# STM32_F4VE.net
KiCad netlist of a schematic drawn in Altium Designer
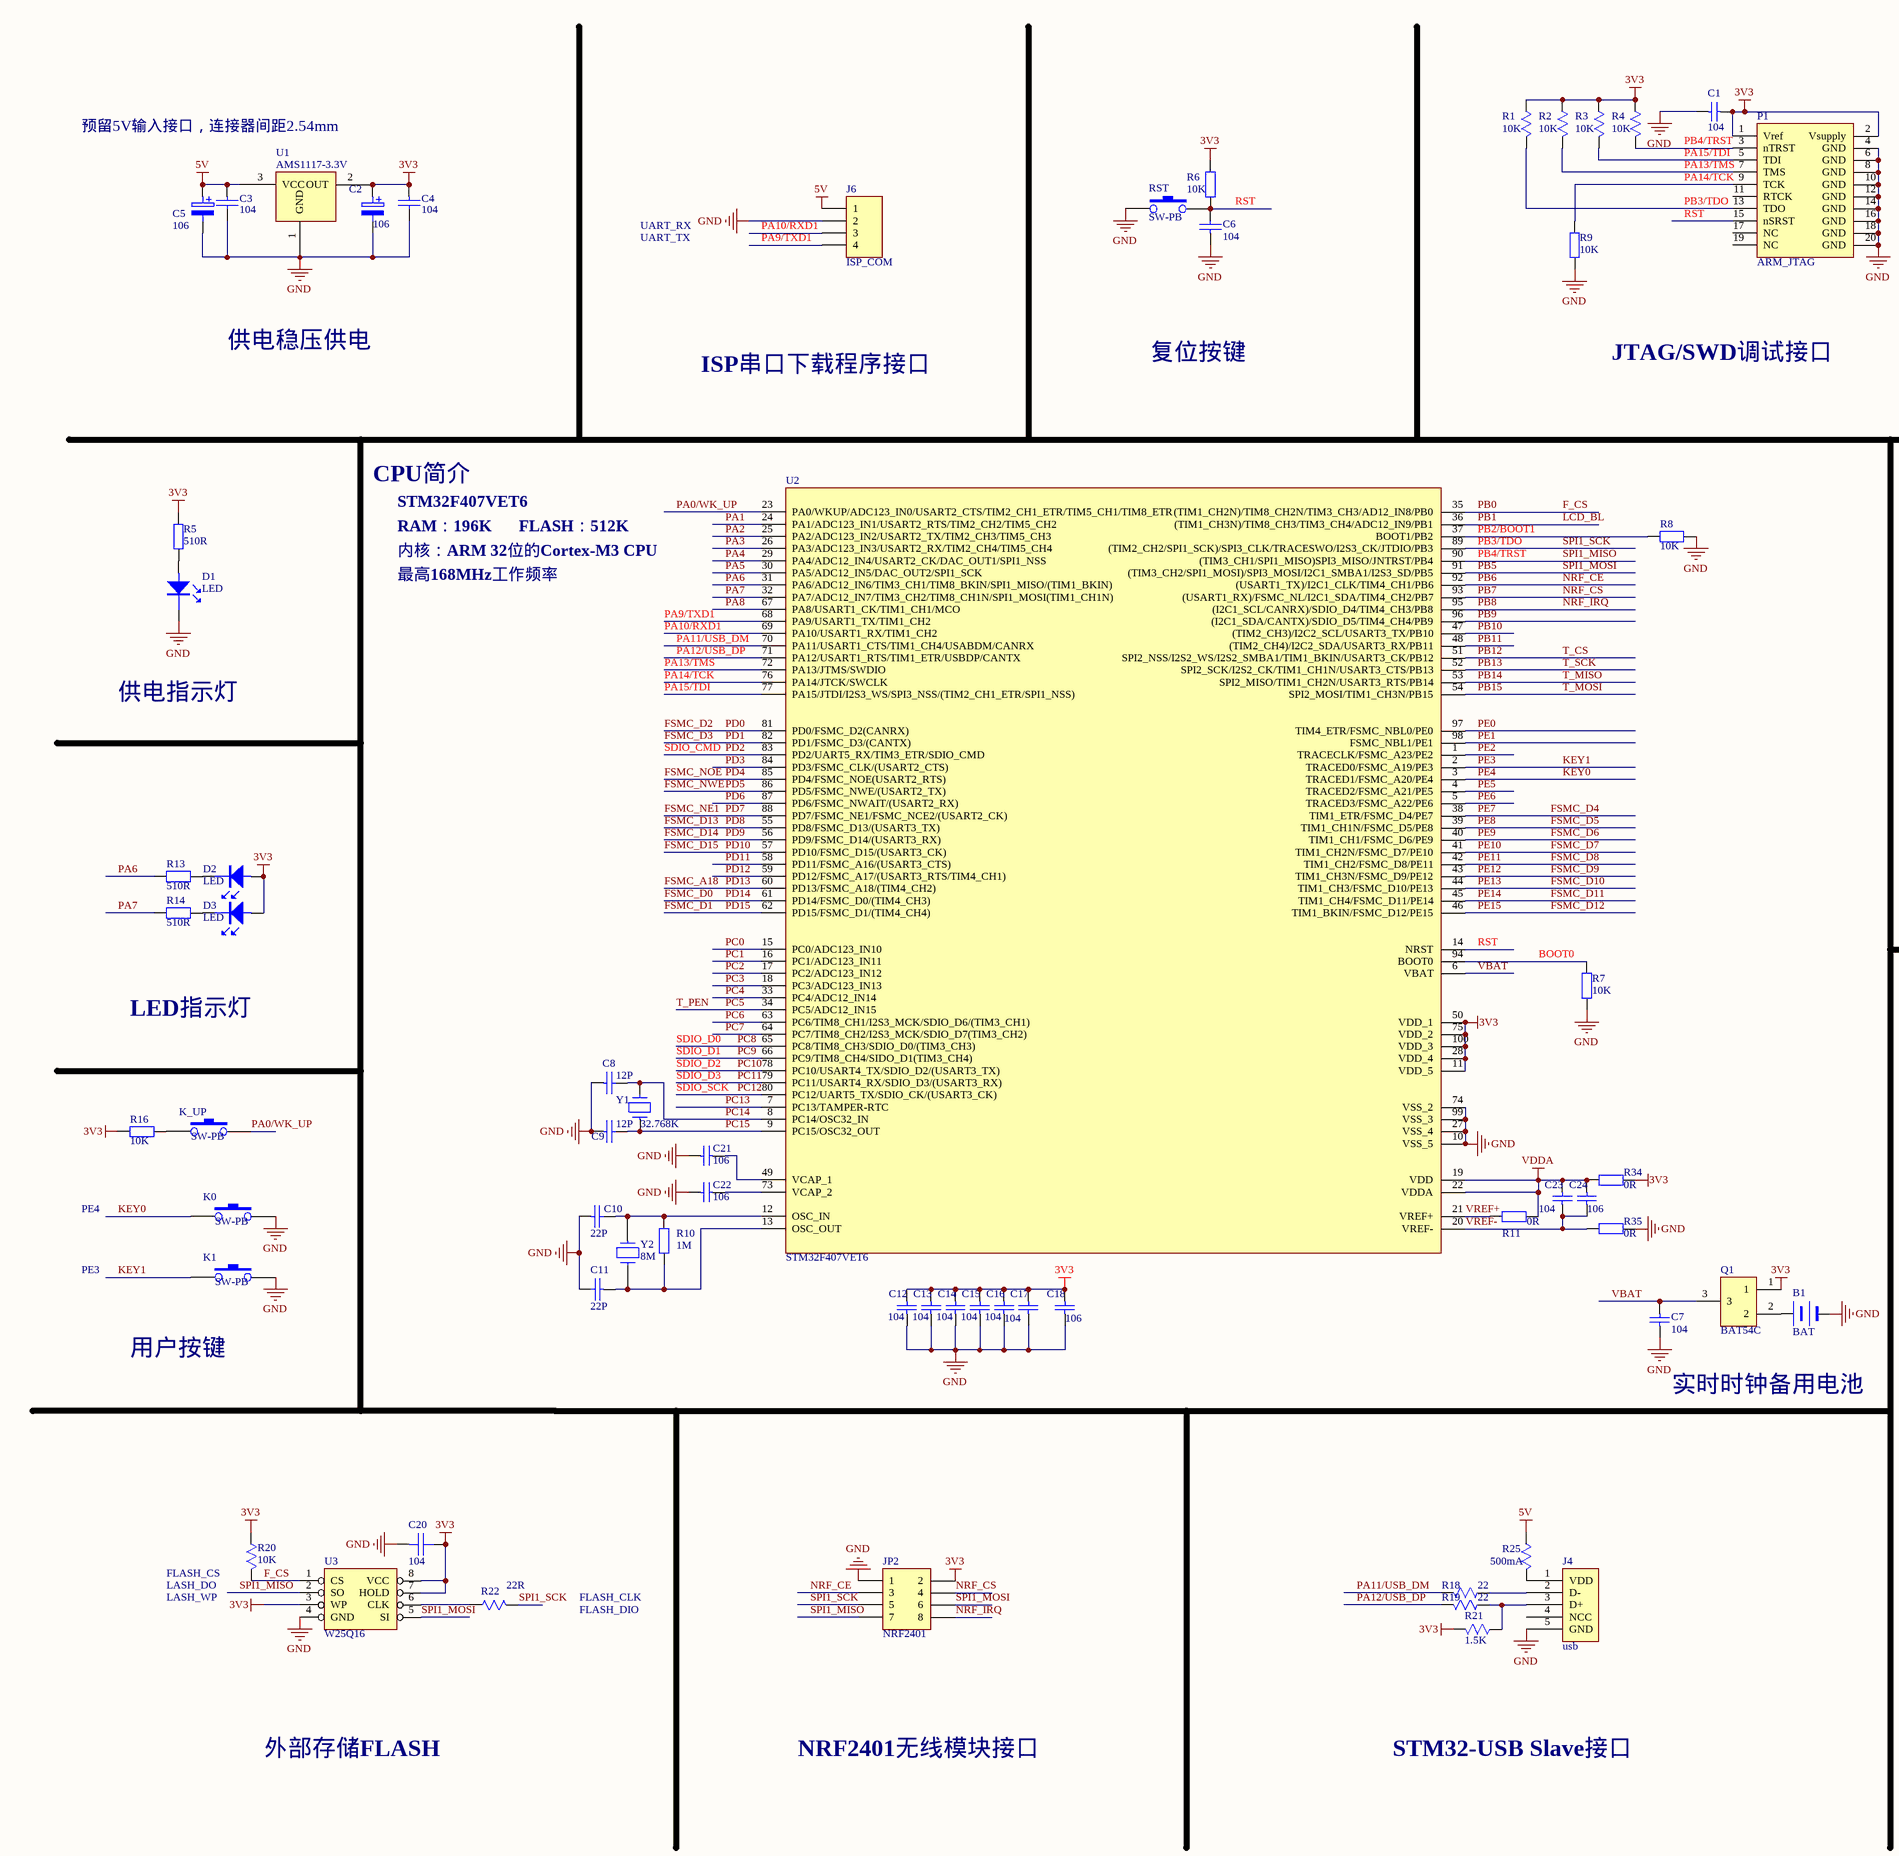
[diagram p0: STM32_F4VE.SchDoc, left]
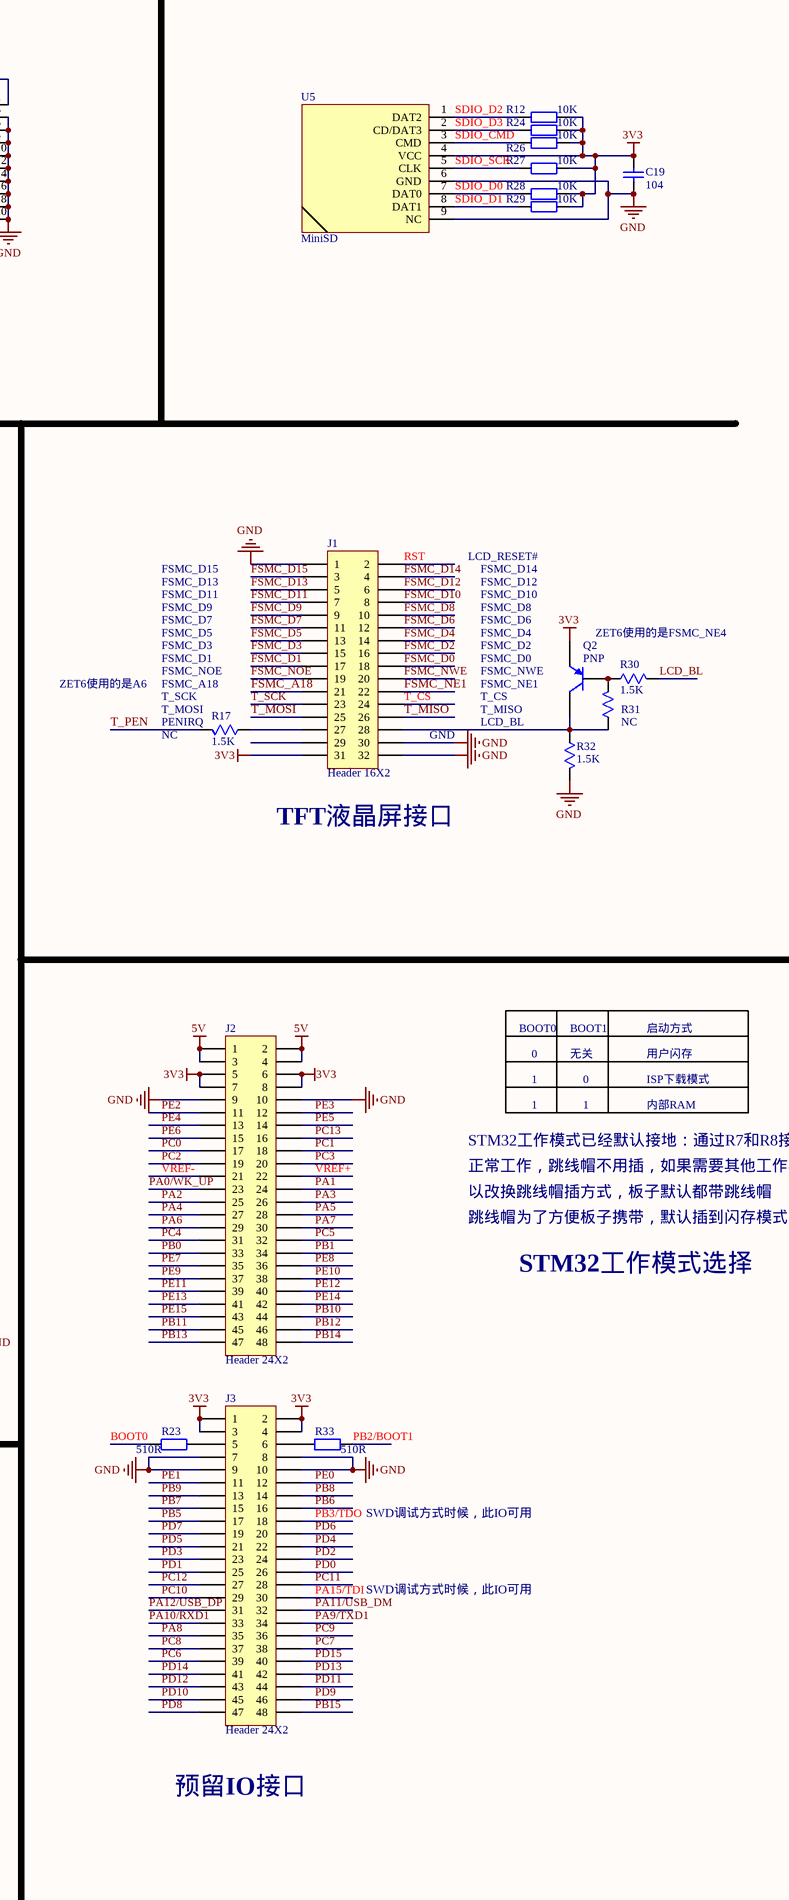
[diagram p1: STM32_F4VE.SchDoc, right]

(export (version "E")
  (design (tool "Eeschema 10.0.6"))
  (components
    (comp (ref "B1") (value "BAT") (footprint "BAT") (libsource (lib "*") (part "BATTERY")))
    (comp (ref "C1")
      (value "104")
      (footprint "RC0603")
      (description "Capacitor")
      (fields (field (name "PUBLISHER") "Altium Limited"))
      (libsource (lib "*") (part "Cap"))
    )
    (comp (ref "C2") (value "106") (footprint "RC0805") (libsource (lib "*") (part "ELECTRO2")))
    (comp (ref "C3")
      (value "104")
      (footprint "RC0603")
      (description "Capacitor")
      (libsource (lib "*") (part "CAP"))
    )
    (comp (ref "C4")
      (value "104")
      (footprint "RC0603")
      (description "Capacitor")
      (libsource (lib "*") (part "CAP"))
    )
    (comp (ref "C5") (value "106") (footprint "RC0805") (libsource (lib "*") (part "ELECTRO2")))
    (comp (ref "C6")
      (value "104")
      (footprint "RC0603")
      (description "Capacitor")
      (libsource (lib "") (part "CAP_1"))
    )
    (comp (ref "C7")
      (value "104")
      (footprint "RC0603")
      (description "Capacitor")
      (fields (field (name "PUBLISHER") "Altium Limited"))
      (libsource (lib "") (part "Cap_1"))
    )
    (comp (ref "C8") (value "12P") (footprint "RC0603") (libsource (lib "") (part "CAP_2")))
    (comp (ref "C9") (value "12P") (footprint "RC0603") (libsource (lib "") (part "CAP_2")))
    (comp (ref "C10")
      (value "22P")
      (footprint "RC0603")
      (description "Capacitor")
      (libsource (lib "") (part "CAP_1"))
    )
    (comp (ref "C11")
      (value "22P")
      (footprint "RC0603")
      (description "Capacitor")
      (libsource (lib "") (part "CAP_1"))
    )
    (comp (ref "C12")
      (value "104")
      (footprint "RC0603")
      (description "Capacitor")
      (fields (field (name "PUBLISHER") "Altium Limited"))
      (libsource (lib "*") (part "Cap"))
    )
    (comp (ref "C13")
      (value "104")
      (footprint "RC0603")
      (description "Capacitor")
      (fields (field (name "PUBLISHER") "Altium Limited"))
      (libsource (lib "*") (part "Cap"))
    )
    (comp (ref "C14")
      (value "104")
      (footprint "RC0603")
      (description "Capacitor")
      (fields (field (name "PUBLISHER") "Altium Limited"))
      (libsource (lib "*") (part "Cap"))
    )
    (comp (ref "C15")
      (value "104")
      (footprint "RC0603")
      (description "Capacitor")
      (fields (field (name "PUBLISHER") "Altium Limited"))
      (libsource (lib "*") (part "Cap"))
    )
    (comp (ref "C16")
      (value "104")
      (footprint "RC0603")
      (description "Capacitor")
      (fields (field (name "PUBLISHER") "Altium Limited"))
      (libsource (lib "*") (part "Cap"))
    )
    (comp (ref "C17")
      (value "104")
      (footprint "RC0603")
      (description "Capacitor")
      (fields (field (name "PUBLISHER") "Altium Limited"))
      (libsource (lib "*") (part "Cap"))
    )
    (comp (ref "C18")
      (value "106")
      (footprint "RC0805")
      (description "Capacitor")
      (fields (field (name "PUBLISHER") "Altium Limited"))
      (libsource (lib "*") (part "Cap"))
    )
    (comp (ref "C19")
      (value "104")
      (footprint "RC0603")
      (description "Capacitor (Semiconductor SIM Model)")
      (fields (field (name "PUBLISHER") "Altium Limited"))
      (libsource (lib "*") (part "Cap Semi"))
    )
    (comp (ref "C20") (value "104") (footprint "RC0603") (libsource (lib "YT1_SCH_99SE") (part "CAP")))
    (comp (ref "C21")
      (value "106")
      (footprint "RC0805")
      (description "Capacitor")
      (fields (field (name "PUBLISHER") "Altium Limited"))
      (libsource (lib "*") (part "Cap"))
    )
    (comp (ref "C22")
      (value "106")
      (footprint "RC0805")
      (description "Capacitor")
      (fields (field (name "PUBLISHER") "Altium Limited"))
      (libsource (lib "*") (part "Cap"))
    )
    (comp (ref "C23")
      (value "104")
      (footprint "RC0603")
      (description "Capacitor")
      (fields (field (name "PUBLISHER") "Altium Limited"))
      (libsource (lib "*") (part "Cap"))
    )
    (comp (ref "C24")
      (value "106")
      (footprint "RC0805")
      (description "Capacitor")
      (fields (field (name "PUBLISHER") "Altium Limited"))
      (libsource (lib "*") (part "Cap"))
    )
    (comp (ref "D1") (value "LED") (footprint "LED0805") (libsource (lib "*") (part "LED")))
    (comp (ref "D2") (value "LED") (footprint "LED0805") (libsource (lib "*") (part "LED")))
    (comp (ref "D3") (value "LED") (footprint "LED0805") (libsource (lib "*") (part "LED")))
    (comp (ref "J1")
      (value "Header 16X2")
      (footprint "IDE2X16")
      (description "Header, 16-Pin, Dual row")
      (fields (field (name "PUBLISHER") "Altium Limited"))
      (libsource (lib "Miscellaneous Connectors") (part "Header 16X2"))
    )
    (comp (ref "J2")
      (value "Header 24X2")
      (footprint "IDE2X24")
      (description "Header, 24-Pin, Dual row")
      (fields (field (name "PUBLISHER") "Altium Limited"))
      (libsource (lib "Miscellaneous Connectors") (part "Header 24X2"))
    )
    (comp (ref "J3")
      (value "Header 24X2")
      (footprint "IDE2X24")
      (description "Header, 24-Pin, Dual row")
      (fields (field (name "PUBLISHER") "Altium Limited"))
      (libsource (lib "Miscellaneous Connectors") (part "Header 24X2"))
    )
    (comp (ref "J4") (value "usb") (footprint "Mini_USB") (libsource (lib "YT1_SCH_99SE") (part "usb")))
    (comp (ref "J6")
      (value "ISP_COM")
      (footprint "HDR1X4")
      (description "Header, 4-Pin")
      (fields (field (name "PUBLISHER") "Altium Limited"))
      (libsource (lib "Miscellaneous Connectors") (part "Header 4"))
    )
    (comp (ref "JP2")
      (value "NRF2401")
      (footprint "IDE2X4")
      (description "Header, 4-Pin, Dual row")
      (fields (field (name "PUBLISHER") "Altium Limited"))
      (libsource (lib "Miscellaneous Connectors") (part "Header 4X2"))
    )
    (comp (ref "K0") (value "SW-PB") (footprint "SW-SPST") (libsource (lib "*") (part "SW-PB")))
    (comp (ref "K1") (value "SW-PB") (footprint "SW-SPST") (libsource (lib "*") (part "SW-PB")))
    (comp (ref "K_UP") (value "SW-PB") (footprint "SW-SPST") (libsource (lib "*") (part "SW-PB")))
    (comp (ref "P1")
      (value "ARM_JTAG")
      (footprint "JTAG-20P")
      (description "JTAG")
      (libsource (lib "LXKJSJ") (part "JTAG"))
    )
    (comp (ref "Q1")
      (value "BAT54C")
      (footprint "SOT-23-BAT54C")
      (libsource (lib "Newcapec9263") (part "BAT54C"))
    )
    (comp (ref "Q2")
      (value "PNP")
      (footprint "PNP_SOT23")
      (description "PNP Bipolar Transistor")
      (fields (field (name "PUBLISHER") "Altium Limited"))
      (libsource (lib "Miscellaneous Devices") (part "PNP"))
    )
    (comp (ref "R1") (value "10K") (footprint "RC0603") (libsource (lib "YT1_SCH_99SE") (part "RES")))
    (comp (ref "R2") (value "10K") (footprint "RC0603") (libsource (lib "YT1_SCH_99SE") (part "RES")))
    (comp (ref "R3") (value "10K") (footprint "RC0603") (libsource (lib "YT1_SCH_99SE") (part "RES")))
    (comp (ref "R4") (value "10K") (footprint "RC0603") (libsource (lib "YT1_SCH_99SE") (part "RES")))
    (comp (ref "R5")
      (value "510R")
      (footprint "RC0603")
      (description "Resistor")
      (libsource (lib "") (part "Res2_2"))
    )
    (comp (ref "R6")
      (value "10K")
      (footprint "RC0603")
      (description "Resistor")
      (libsource (lib "") (part "Res2_1"))
    )
    (comp (ref "R7")
      (value "10K")
      (footprint "RC0603")
      (description "Resistor")
      (libsource (lib "") (part "Res2_2"))
    )
    (comp (ref "R8")
      (value "10K")
      (footprint "RC0603")
      (description "Resistor")
      (libsource (lib "") (part "Res2_3"))
    )
    (comp (ref "R9")
      (value "10K")
      (footprint "RC0603")
      (description "Resistor")
      (libsource (lib "") (part "Res2_2"))
    )
    (comp (ref "R10")
      (value "1M")
      (footprint "RC0603")
      (description "Resistor")
      (libsource (lib "") (part "Res2_1"))
    )
    (comp (ref "R11")
      (value "0R")
      (footprint "RC0603")
      (description "Resistor")
      (libsource (lib "Miscellaneous Devices") (part "Res2"))
    )
    (comp (ref "R12")
      (value "10K")
      (footprint "RC0603")
      (description "Resistor")
      (libsource (lib "Miscellaneous Devices") (part "Res2"))
    )
    (comp (ref "R13")
      (value "510R")
      (footprint "RC0603")
      (description "Resistor")
      (libsource (lib "Miscellaneous Devices") (part "Res2"))
    )
    (comp (ref "R14")
      (value "510R")
      (footprint "RC0603")
      (description "Resistor")
      (libsource (lib "Miscellaneous Devices") (part "Res2"))
    )
    (comp (ref "R16")
      (value "10K")
      (footprint "RC0603")
      (description "Resistor")
      (libsource (lib "") (part "Res2_3"))
    )
    (comp (ref "R17") (value "1.5K") (footprint "RC0603") (libsource (lib "YT1_SCH_99SE") (part "RES")))
    (comp (ref "R18") (value "22") (footprint "RC0603") (libsource (lib "YT1_SCH_99SE") (part "RES")))
    (comp (ref "R19") (value "22") (footprint "RC0603") (libsource (lib "YT1_SCH_99SE") (part "RES")))
    (comp (ref "R20") (value "10K") (footprint "RC0603") (libsource (lib "YT1_SCH_99SE") (part "RES")))
    (comp (ref "R21") (value "1.5K") (footprint "RC0603") (libsource (lib "YT1_SCH_99SE") (part "RES")))
    (comp (ref "R22") (value "22R") (footprint "RC0603") (libsource (lib "YT1_SCH_99SE") (part "RES")))
    (comp (ref "R23")
      (value "510R")
      (footprint "RC0603")
      (description "Resistor")
      (libsource (lib "Miscellaneous Devices") (part "Res2"))
    )
    (comp (ref "R24")
      (value "10K")
      (footprint "RC0603")
      (description "Resistor")
      (libsource (lib "Miscellaneous Devices") (part "Res2"))
    )
    (comp (ref "R25") (value "500mA") (footprint "RC0805") (libsource (lib "YT1_SCH_99SE") (part "RES")))
    (comp (ref "R26")
      (value "10K")
      (footprint "RC0603")
      (description "Resistor")
      (libsource (lib "Miscellaneous Devices") (part "Res2"))
    )
    (comp (ref "R27")
      (value "10K")
      (footprint "RC0603")
      (description "Resistor")
      (libsource (lib "Miscellaneous Devices") (part "Res2"))
    )
    (comp (ref "R28")
      (value "10K")
      (footprint "RC0603")
      (description "Resistor")
      (libsource (lib "Miscellaneous Devices") (part "Res2"))
    )
    (comp (ref "R29")
      (value "10K")
      (footprint "RC0603")
      (description "Resistor")
      (libsource (lib "Miscellaneous Devices") (part "Res2"))
    )
    (comp (ref "R30") (value "1.5K") (footprint "RC0603") (libsource (lib "YT1_SCH_99SE") (part "RES")))
    (comp (ref "R31") (value "NC") (footprint "RC0603") (libsource (lib "YT1_SCH_99SE") (part "RES")))
    (comp (ref "R32") (value "1.5K") (footprint "RC0603") (libsource (lib "YT1_SCH_99SE") (part "RES")))
    (comp (ref "R33")
      (value "510R")
      (footprint "RC0603")
      (description "Resistor")
      (libsource (lib "Miscellaneous Devices") (part "Res2"))
    )
    (comp (ref "R34")
      (value "0R")
      (footprint "RC0603")
      (description "Resistor")
      (libsource (lib "Miscellaneous Devices") (part "Res2"))
    )
    (comp (ref "R35")
      (value "0R")
      (footprint "RC0603")
      (description "Resistor")
      (libsource (lib "Miscellaneous Devices") (part "Res2"))
    )
    (comp (ref "RST") (value "SW-PB") (footprint "SW-SPST") (libsource (lib "*") (part "SW-PB")))
    (comp (ref "U1") (value "AMS1117-3.3V") (footprint "SOT-223") (libsource (lib "*") (part "11")))
    (comp (ref "U2") (value "STM32F407VET6") (libsource (lib "STM32_F4VE") (part "STM32F407VET6")))
    (comp (ref "U3") (value "W25Q16") (footprint "SOP8L") (libsource (lib "YT1_SCH_99SE") (part "W25X16")))
    (comp (ref "U5") (value "MiniSD") (footprint "TF_SD") (libsource (lib "STM32_RF") (part "MiniSD")))
    (comp (ref "Y1")
      (value "32.768K")
      (footprint "JZ32768")
      (description "晶振")
      (libsource (lib "") (part "CRYSTAL_1"))
    )
    (comp (ref "Y2")
      (value "8M")
      (footprint "49S_SMD")
      (description "Crystal")
      (libsource (lib "*") (part "CRYSTAL"))
    )
  )
  (nets
    (net (code "1") (name "/BOOT0") (class "Default")
      (node (ref "R23") (pin "1") (pinfunction "1_1") (pintype "passive"))
      (node (ref "R7") (pin "2") (pinfunction "2_2") (pintype "passive"))
      (node (ref "U2") (pin "94") (pinfunction "BOOT0_94") (pintype "passive"))
    )
    (net (code "2") (name "/FSMC_A18") (class "Default")
      (node (ref "J1") (pin "21") (pinfunction "21_21") (pintype "passive"))
      (node (ref "J3") (pin "42") (pinfunction "42_42") (pintype "passive"))
      (node (ref "U2") (pin "60") (pinfunction "PD13/FSMC_A18/(TIM4_CH2)_60") (pintype "passive"))
    )
    (net (code "3") (name "/FSMC_D0") (class "Default")
      (node (ref "J1") (pin "18") (pinfunction "18_18") (pintype "passive"))
      (node (ref "J3") (pin "41") (pinfunction "41_41") (pintype "passive"))
      (node (ref "U2") (pin "61") (pinfunction "PD14/FSMC_D0/(TIM4_CH3)_61") (pintype "passive"))
    )
    (net (code "4") (name "/FSMC_D1") (class "Default")
      (node (ref "J1") (pin "17") (pinfunction "17_17") (pintype "passive"))
      (node (ref "J3") (pin "40") (pinfunction "40_40") (pintype "passive"))
      (node (ref "U2") (pin "62") (pinfunction "PD15/FSMC_D1/(TIM4_CH4)_62") (pintype "passive"))
    )
    (net (code "5") (name "/FSMC_D2") (class "Default")
      (node (ref "J1") (pin "16") (pinfunction "16_16") (pintype "passive"))
      (node (ref "J3") (pin "26") (pinfunction "26_26") (pintype "passive"))
      (node (ref "U2") (pin "81") (pinfunction "PD0/FSMC_D2(CANRX)_81") (pintype "passive"))
    )
    (net (code "6") (name "/FSMC_D3") (class "Default")
      (node (ref "J1") (pin "15") (pinfunction "15_15") (pintype "passive"))
      (node (ref "J3") (pin "25") (pinfunction "25_25") (pintype "passive"))
      (node (ref "U2") (pin "82") (pinfunction "PD1/FSMC_D3/(CANTX)_82") (pintype "passive"))
    )
    (net (code "7") (name "/FSMC_D4") (class "Default")
      (node (ref "J1") (pin "14") (pinfunction "14_14") (pintype "passive"))
      (node (ref "J2") (pin "35") (pinfunction "35_35") (pintype "passive"))
      (node (ref "U2") (pin "38") (pinfunction "TIM1_ETR/FSMC_D4/PE7_38") (pintype "passive"))
    )
    (net (code "8") (name "/FSMC_D5") (class "Default")
      (node (ref "J1") (pin "13") (pinfunction "13_13") (pintype "passive"))
      (node (ref "J2") (pin "36") (pinfunction "36_36") (pintype "passive"))
      (node (ref "U2") (pin "39") (pinfunction "TIM1_CH1N/FSMC_D5/PE8_39") (pintype "passive"))
    )
    (net (code "9") (name "/FSMC_D6") (class "Default")
      (node (ref "J1") (pin "12") (pinfunction "12_12") (pintype "passive"))
      (node (ref "J2") (pin "37") (pinfunction "37_37") (pintype "passive"))
      (node (ref "U2") (pin "40") (pinfunction "TIM1_CH1/FSMC_D6/PE9_40") (pintype "passive"))
    )
    (net (code "10") (name "/FSMC_D7") (class "Default")
      (node (ref "J1") (pin "11") (pinfunction "11_11") (pintype "passive"))
      (node (ref "J2") (pin "38") (pinfunction "38_38") (pintype "passive"))
      (node (ref "U2") (pin "41") (pinfunction "TIM1_CH2N/FSMC_D7/PE10_41") (pintype "passive"))
    )
    (net (code "11") (name "/FSMC_D8") (class "Default")
      (node (ref "J1") (pin "10") (pinfunction "10_10") (pintype "passive"))
      (node (ref "J2") (pin "39") (pinfunction "39_39") (pintype "passive"))
      (node (ref "U2") (pin "42") (pinfunction "TIM1_CH2/FSMC_D8/PE11_42") (pintype "passive"))
    )
    (net (code "12") (name "/FSMC_D9") (class "Default")
      (node (ref "J1") (pin "9") (pinfunction "9_9") (pintype "passive"))
      (node (ref "J2") (pin "40") (pinfunction "40_40") (pintype "passive"))
      (node (ref "U2") (pin "43") (pinfunction "TIM1_CH3N/FSMC_D9/PE12_43") (pintype "passive"))
    )
    (net (code "13") (name "/FSMC_D10") (class "Default")
      (node (ref "J1") (pin "8") (pinfunction "8_8") (pintype "passive"))
      (node (ref "J2") (pin "41") (pinfunction "41_41") (pintype "passive"))
      (node (ref "U2") (pin "44") (pinfunction "TIM1_CH3/FSMC_D10/PE13_44") (pintype "passive"))
    )
    (net (code "14") (name "/FSMC_D11") (class "Default")
      (node (ref "J1") (pin "7") (pinfunction "7_7") (pintype "passive"))
      (node (ref "J2") (pin "42") (pinfunction "42_42") (pintype "passive"))
      (node (ref "U2") (pin "45") (pinfunction "TIM1_CH4/FSMC_D11/PE14_45") (pintype "passive"))
    )
    (net (code "15") (name "/FSMC_D12") (class "Default")
      (node (ref "J1") (pin "6") (pinfunction "6_6") (pintype "passive"))
      (node (ref "J2") (pin "43") (pinfunction "43_43") (pintype "passive"))
      (node (ref "U2") (pin "46") (pinfunction "TIM1_BKIN/FSMC_D12/PE15_46") (pintype "passive"))
    )
    (net (code "16") (name "/FSMC_D13") (class "Default")
      (node (ref "J1") (pin "5") (pinfunction "5_5") (pintype "passive"))
      (node (ref "J3") (pin "47") (pinfunction "47_47") (pintype "passive"))
      (node (ref "U2") (pin "55") (pinfunction "PD8/FSMC_D13/(USART3_TX)_55") (pintype "passive"))
    )
    (net (code "17") (name "/FSMC_D14") (class "Default")
      (node (ref "J1") (pin "4") (pinfunction "4_4") (pintype "passive"))
      (node (ref "J3") (pin "46") (pinfunction "46_46") (pintype "passive"))
      (node (ref "U2") (pin "56") (pinfunction "PD9/FSMC_D14/(USART3_RX)_56") (pintype "passive"))
    )
    (net (code "18") (name "/FSMC_D15") (class "Default")
      (node (ref "J1") (pin "3") (pinfunction "3_3") (pintype "passive"))
      (node (ref "J3") (pin "45") (pinfunction "45_45") (pintype "passive"))
      (node (ref "U2") (pin "57") (pinfunction "PD10/FSMC_D15/(USART3_CK)_57") (pintype "passive"))
    )
    (net (code "19") (name "/FSMC_NE1") (class "Default")
      (node (ref "J1") (pin "22") (pinfunction "22_22") (pintype "passive"))
      (node (ref "J3") (pin "19") (pinfunction "19_19") (pintype "passive"))
      (node (ref "U2") (pin "88") (pinfunction "PD7/FSMC_NE1/FSMC_NCE2/(USART2_CK)_88") (pintype "passive"))
    )
    (net (code "20") (name "/FSMC_NOE") (class "Default")
      (node (ref "J1") (pin "19") (pinfunction "19_19") (pintype "passive"))
      (node (ref "J3") (pin "22") (pinfunction "22_22") (pintype "passive"))
      (node (ref "U2") (pin "85") (pinfunction "PD4/FSMC_NOE(USART2_RTS)_85") (pintype "passive"))
    )
    (net (code "21") (name "/FSMC_NWE") (class "Default")
      (node (ref "J1") (pin "20") (pinfunction "20_20") (pintype "passive"))
      (node (ref "J3") (pin "21") (pinfunction "21_21") (pintype "passive"))
      (node (ref "U2") (pin "86") (pinfunction "PD5/FSMC_NWE/(USART2_TX)_86") (pintype "passive"))
    )
    (net (code "22") (name "/F_CS") (class "Default")
      (node (ref "J2") (pin "33") (pinfunction "33_33") (pintype "passive"))
      (node (ref "R20") (pin "2") (pinfunction "2_2") (pintype "passive"))
      (node (ref "U2") (pin "35") (pinfunction "(TIM1_CH2N)/TIM8_CH2N/TIM3_CH3/AD12_IN8/PB0_35") (pintype "passive"))
      (node (ref "U3") (pin "1") (pinfunction "CS_1") (pintype "passive"))
    )
    (net (code "23") (name "/KEY0") (class "Default")
      (node (ref "J2") (pin "13") (pinfunction "13_13") (pintype "passive"))
      (node (ref "K0") (pin "1") (pinfunction "1_1") (pintype "passive"))
      (node (ref "U2") (pin "3") (pinfunction "TRACED1/FSMC_A20/PE4_3") (pintype "passive"))
    )
    (net (code "24") (name "/KEY1") (class "Default")
      (node (ref "J2") (pin "12") (pinfunction "12_12") (pintype "passive"))
      (node (ref "K1") (pin "1") (pinfunction "1_1") (pintype "passive"))
      (node (ref "U2") (pin "2") (pinfunction "TRACED0/FSMC_A19/PE3_2") (pintype "passive"))
    )
    (net (code "25") (name "/LCD_BL") (class "Default")
      (node (ref "J2") (pin "34") (pinfunction "34_34") (pintype "passive"))
      (node (ref "R30") (pin "2") (pinfunction "2_2") (pintype "passive"))
      (node (ref "U2") (pin "36") (pinfunction "(TIM1_CH3N)/TIM8_CH3/TIM3_CH4/ADC12_IN9/PB1_36") (pintype "passive"))
    )
    (net (code "26") (name "/NRF_CE") (class "Default")
      (node (ref "J3") (pin "16") (pinfunction "16_16") (pintype "passive"))
      (node (ref "JP2") (pin "3") (pinfunction "3_3") (pintype "passive"))
      (node (ref "U2") (pin "92") (pinfunction "(USART1_TX)/I2C1_CLK/TIM4_CH1/PB6_92") (pintype "passive"))
    )
    (net (code "27") (name "/NRF_CS") (class "Default")
      (node (ref "J3") (pin "15") (pinfunction "15_15") (pintype "passive"))
      (node (ref "JP2") (pin "4") (pinfunction "4_4") (pintype "passive"))
      (node (ref "U2") (pin "93") (pinfunction "(USART1_RX)/FSMC_NL/I2C1_SDA/TIM4_CH2/PB7_93") (pintype "passive"))
    )
    (net (code "28") (name "/NRF_IRQ") (class "Default")
      (node (ref "J3") (pin "14") (pinfunction "14_14") (pintype "passive"))
      (node (ref "JP2") (pin "8") (pinfunction "8_8") (pintype "passive"))
      (node (ref "U2") (pin "95") (pinfunction "(I2C1_SCL/CANRX)/SDIO_D4/TIM4_CH3/PB8_95") (pintype "passive"))
    )
    (net (code "29") (name "/PA0{slash}WK_UP") (class "Default")
      (node (ref "J2") (pin "23") (pinfunction "23_23") (pintype "passive"))
      (node (ref "K_UP") (pin "2") (pinfunction "2_2") (pintype "passive"))
      (node (ref "U2") (pin "23") (pinfunction "PA0/WKUP/ADC123_IN0/USART2_CTS/TIM2_CH1_ETR/TIM5_CH1/TIM8_ETR_23") (pintype "passive"))
    )
    (net (code "30") (name "/PA1") (class "Default")
      (node (ref "J2") (pin "24") (pinfunction "24_24") (pintype "passive"))
      (node (ref "U2") (pin "24") (pinfunction "PA1/ADC123_IN1/USART2_RTS/TIM2_CH2/TIM5_CH2_24") (pintype "passive"))
    )
    (net (code "31") (name "/PA2") (class "Default")
      (node (ref "J2") (pin "25") (pinfunction "25_25") (pintype "passive"))
      (node (ref "U2") (pin "25") (pinfunction "PA2/ADC123_IN2/USART2_TX/TIM2_CH3/TIM5_CH3_25") (pintype "passive"))
    )
    (net (code "32") (name "/PA3") (class "Default")
      (node (ref "J2") (pin "26") (pinfunction "26_26") (pintype "passive"))
      (node (ref "U2") (pin "26") (pinfunction "PA3/ADC123_IN3/USART2_RX/TIM2_CH4/TIM5_CH4_26") (pintype "passive"))
    )
    (net (code "33") (name "/PA4") (class "Default")
      (node (ref "J2") (pin "27") (pinfunction "27_27") (pintype "passive"))
      (node (ref "U2") (pin "29") (pinfunction "PA4/ADC12_IN4/USART2_CK/DAC_OUT1/SPI1_NSS_29") (pintype "passive"))
    )
    (net (code "34") (name "/PA5") (class "Default")
      (node (ref "J2") (pin "28") (pinfunction "28_28") (pintype "passive"))
      (node (ref "U2") (pin "30") (pinfunction "PA5/ADC12_IN5/DAC_OUT2/SPI1_SCK_30") (pintype "passive"))
    )
    (net (code "35") (name "/PA6") (class "Default")
      (node (ref "J2") (pin "29") (pinfunction "29_29") (pintype "passive"))
      (node (ref "R13") (pin "1") (pinfunction "1_1") (pintype "passive"))
      (node (ref "U2") (pin "31") (pinfunction "PA6/ADC12_IN6/TIM3_CH1/TIM8_BKIN/SPI1_MISO/(TIM1_BKIN)_31") (pintype "passive"))
    )
    (net (code "36") (name "/PA7") (class "Default")
      (node (ref "J2") (pin "30") (pinfunction "30_30") (pintype "passive"))
      (node (ref "R14") (pin "1") (pinfunction "1_1") (pintype "passive"))
      (node (ref "U2") (pin "32") (pinfunction "PA7/ADC12_IN7/TIM3_CH2/TIM8_CH1N/SPI1_MOSI(TIM1_CH1N)_32") (pintype "passive"))
    )
    (net (code "37") (name "/PA8") (class "Default")
      (node (ref "J3") (pin "35") (pinfunction "35_35") (pintype "passive"))
      (node (ref "U2") (pin "67") (pinfunction "PA8/USART1_CK/TIM1_CH1/MCO_67") (pintype "passive"))
    )
    (net (code "38") (name "/PA9{slash}TXD1") (class "Default")
      (node (ref "J3") (pin "34") (pinfunction "34_34") (pintype "passive"))
      (node (ref "J6") (pin "4") (pinfunction "4_4") (pintype "passive"))
      (node (ref "U2") (pin "68") (pinfunction "PA9/USART1_TX/TIM1_CH2_68") (pintype "passive"))
    )
    (net (code "39") (name "/PA10{slash}RXD1") (class "Default")
      (node (ref "J3") (pin "33") (pinfunction "33_33") (pintype "passive"))
      (node (ref "J6") (pin "3") (pinfunction "3_3") (pintype "passive"))
      (node (ref "U2") (pin "69") (pinfunction "PA10/USART1_RX/TIM1_CH2_69") (pintype "passive"))
    )
    (net (code "40") (name "/PA11{slash}USB_DM") (class "Default")
      (node (ref "J3") (pin "32") (pinfunction "32_32") (pintype "passive"))
      (node (ref "R18") (pin "2") (pinfunction "2_2") (pintype "passive"))
      (node (ref "U2") (pin "70") (pinfunction "PA11/USART1_CTS/TIM1_CH4/USABDM/CANRX_70") (pintype "passive"))
    )
    (net (code "41") (name "/PA12{slash}USB_DP") (class "Default")
      (node (ref "J3") (pin "31") (pinfunction "31_31") (pintype "passive"))
      (node (ref "R19") (pin "2") (pinfunction "2_2") (pintype "passive"))
      (node (ref "U2") (pin "71") (pinfunction "PA12/USART1_RTS/TIM1_ETR/USBDP/CANTX_71") (pintype "passive"))
    )
    (net (code "42") (name "/PA13{slash}TMS") (class "Default")
      (node (ref "P1") (pin "7") (pinfunction "TMS_7") (pintype "passive"))
      (node (ref "R2") (pin "2") (pinfunction "2_2") (pintype "passive"))
      (node (ref "U2") (pin "72") (pinfunction "PA13/JTMS/SWDIO_72") (pintype "passive"))
    )
    (net (code "43") (name "/PA14{slash}TCK") (class "Default")
      (node (ref "P1") (pin "9") (pinfunction "TCK_9") (pintype "passive"))
      (node (ref "R9") (pin "2") (pinfunction "2_2") (pintype "passive"))
      (node (ref "U2") (pin "76") (pinfunction "PA14/JTCK/SWCLK_76") (pintype "passive"))
    )
    (net (code "44") (name "/PA15{slash}TDI") (class "Default")
      (node (ref "J3") (pin "30") (pinfunction "30_30") (pintype "passive"))
      (node (ref "P1") (pin "5") (pinfunction "TDI_5") (pintype "passive"))
      (node (ref "R3") (pin "2") (pinfunction "2_2") (pintype "passive"))
      (node (ref "U2") (pin "77") (pinfunction "PA15/JTDI/I2S3_WS/SPI3_NSS/(TIM2_CH1_ETR/SPI1_NSS)_77") (pintype "passive"))
    )
    (net (code "45") (name "/PB2{slash}BOOT1") (class "Default")
      (node (ref "R33") (pin "2") (pinfunction "2_2") (pintype "passive"))
      (node (ref "R8") (pin "2") (pinfunction "2_2") (pintype "passive"))
      (node (ref "U2") (pin "37") (pinfunction "BOOT1/PB2_37") (pintype "passive"))
    )
    (net (code "46") (name "/PB3{slash}TDO") (class "Default")
      (node (ref "J3") (pin "18") (pinfunction "18_18") (pintype "passive"))
      (node (ref "JP2") (pin "5") (pinfunction "5_5") (pintype "passive"))
      (node (ref "P1") (pin "13") (pinfunction "TDO_13") (pintype "passive"))
      (node (ref "R1") (pin "2") (pinfunction "2_2") (pintype "passive"))
      (node (ref "R22") (pin "2") (pinfunction "2_2") (pintype "passive"))
      (node (ref "U2") (pin "89") (pinfunction "(TIM2_CH2/SPI1_SCK)/SPI3_CLK/TRACESWO/I2S3_CK/JTDIO/PB3_89") (pintype "passive"))
    )
    (net (code "47") (name "/PB4{slash}TRST") (class "Default")
      (node (ref "JP2") (pin "7") (pinfunction "7_7") (pintype "passive"))
      (node (ref "P1") (pin "3") (pinfunction "nTRST_3") (pintype "passive"))
      (node (ref "R4") (pin "2") (pinfunction "2_2") (pintype "passive"))
      (node (ref "U2") (pin "90") (pinfunction "(TIM3_CH1/SPI1_MISO)SPI3_MISO/JNTRST/PB4_90") (pintype "passive"))
      (node (ref "U3") (pin "2") (pinfunction "SO_2") (pintype "passive"))
    )
    (net (code "48") (name "/PB5") (class "Default")
      (node (ref "J3") (pin "17") (pinfunction "17_17") (pintype "passive"))
      (node (ref "JP2") (pin "6") (pinfunction "6_6") (pintype "passive"))
      (node (ref "U2") (pin "91") (pinfunction "(TIM3_CH2/SPI1_MOSI)/SPI3_MOSI/I2C1_SMBA1/I2S3_SD/PB5_91") (pintype "passive"))
      (node (ref "U3") (pin "5") (pinfunction "SI_5") (pintype "passive"))
    )
    (net (code "49") (name "/PB9") (class "Default")
      (node (ref "J3") (pin "13") (pinfunction "13_13") (pintype "passive"))
      (node (ref "U2") (pin "96") (pinfunction "(I2C1_SDA/CANTX)/SDIO_D5/TIM4_CH4/PB9_96") (pintype "passive"))
    )
    (net (code "50") (name "/PB10") (class "Default")
      (node (ref "J2") (pin "44") (pinfunction "44_44") (pintype "passive"))
      (node (ref "U2") (pin "47") (pinfunction "(TIM2_CH3)/I2C2_SCL/USART3_TX/PB10_47") (pintype "passive"))
    )
    (net (code "51") (name "/PB11") (class "Default")
      (node (ref "J2") (pin "45") (pinfunction "45_45") (pintype "passive"))
      (node (ref "U2") (pin "48") (pinfunction "(TIM2_CH4)/I2C2_SDA/USART3_RX/PB11_48") (pintype "passive"))
    )
    (net (code "52") (name "/PB12") (class "Default")
      (node (ref "J1") (pin "24") (pinfunction "24_24") (pintype "passive"))
      (node (ref "J2") (pin "46") (pinfunction "46_46") (pintype "passive"))
      (node (ref "U2") (pin "51") (pinfunction "SPI2_NSS/I2S2_WS/I2S2_SMBA1/TIM1_BKIN/USART3_CK/PB12_51") (pintype "passive"))
    )
    (net (code "53") (name "/PB13") (class "Default")
      (node (ref "J1") (pin "23") (pinfunction "23_23") (pintype "passive"))
      (node (ref "J2") (pin "47") (pinfunction "47_47") (pintype "passive"))
      (node (ref "U2") (pin "52") (pinfunction "SPI2_SCK/I2S2_CK/TIM1_CH1N/USART3_CTS/PB13_52") (pintype "passive"))
    )
    (net (code "54") (name "/PB14") (class "Default")
      (node (ref "J1") (pin "26") (pinfunction "26_26") (pintype "passive"))
      (node (ref "J2") (pin "48") (pinfunction "48_48") (pintype "passive"))
      (node (ref "U2") (pin "53") (pinfunction "SPI2_MISO/TIM1_CH2N/USART3_RTS/PB14_53") (pintype "passive"))
    )
    (net (code "55") (name "/PB15") (class "Default")
      (node (ref "J1") (pin "25") (pinfunction "25_25") (pintype "passive"))
      (node (ref "J3") (pin "48") (pinfunction "48_48") (pintype "passive"))
      (node (ref "U2") (pin "54") (pinfunction "SPI2_MOSI/TIM1_CH3N/PB15_54") (pintype "passive"))
    )
    (net (code "56") (name "/PC0") (class "Default")
      (node (ref "J2") (pin "17") (pinfunction "17_17") (pintype "passive"))
      (node (ref "U2") (pin "15") (pinfunction "PC0/ADC123_IN10_15") (pintype "passive"))
    )
    (net (code "57") (name "/PC1") (class "Default")
      (node (ref "J2") (pin "18") (pinfunction "18_18") (pintype "passive"))
      (node (ref "U2") (pin "16") (pinfunction "PC1/ADC123_IN11_16") (pintype "passive"))
    )
    (net (code "58") (name "/PC2") (class "Default")
      (node (ref "J2") (pin "19") (pinfunction "19_19") (pintype "passive"))
      (node (ref "U2") (pin "17") (pinfunction "PC2/ADC123_IN12_17") (pintype "passive"))
    )
    (net (code "59") (name "/PC3") (class "Default")
      (node (ref "J2") (pin "20") (pinfunction "20_20") (pintype "passive"))
      (node (ref "U2") (pin "18") (pinfunction "PC3/ADC123_IN13_18") (pintype "passive"))
    )
    (net (code "60") (name "/PC4") (class "Default")
      (node (ref "J2") (pin "31") (pinfunction "31_31") (pintype "passive"))
      (node (ref "U2") (pin "33") (pinfunction "PC4/ADC12_IN14_33") (pintype "passive"))
    )
    (net (code "61") (name "/PC5") (class "Default")
      (node (ref "J2") (pin "32") (pinfunction "32_32") (pintype "passive"))
      (node (ref "R17") (pin "2") (pinfunction "2_2") (pintype "passive"))
      (node (ref "U2") (pin "34") (pinfunction "PC5/ADC12_IN15_34") (pintype "passive"))
    )
    (net (code "62") (name "/PC6") (class "Default")
      (node (ref "J3") (pin "39") (pinfunction "39_39") (pintype "passive"))
      (node (ref "U2") (pin "63") (pinfunction "PC6/TIM8_CH1/I2S3_MCK/SDIO_D6/(TIM3_CH1)_63") (pintype "passive"))
    )
    (net (code "63") (name "/PC7") (class "Default")
      (node (ref "J3") (pin "38") (pinfunction "38_38") (pintype "passive"))
      (node (ref "U2") (pin "64") (pinfunction "PC7/TIM8_CH2/I2S3_MCK/SDIO_D7(TIM3_CH2)_64") (pintype "passive"))
    )
    (net (code "64") (name "/PC8") (class "Default")
      (node (ref "J3") (pin "37") (pinfunction "37_37") (pintype "passive"))
      (node (ref "R28") (pin "1") (pinfunction "1_1") (pintype "passive"))
      (node (ref "U2") (pin "65") (pinfunction "PC8/TIM8_CH3/SDIO_D0/(TIM3_CH3)_65") (pintype "passive"))
      (node (ref "U5") (pin "7") (pinfunction "DAT0_7") (pintype "passive"))
    )
    (net (code "65") (name "/PC9") (class "Default")
      (node (ref "J3") (pin "36") (pinfunction "36_36") (pintype "passive"))
      (node (ref "R29") (pin "1") (pinfunction "1_1") (pintype "passive"))
      (node (ref "U2") (pin "66") (pinfunction "PC9/TIM8_CH4/SIDO_D1(TIM3_CH4)_66") (pintype "passive"))
      (node (ref "U5") (pin "8") (pinfunction "DAT1_8") (pintype "passive"))
    )
    (net (code "66") (name "/PC10") (class "Default")
      (node (ref "J3") (pin "29") (pinfunction "29_29") (pintype "passive"))
      (node (ref "R12") (pin "1") (pinfunction "1_1") (pintype "passive"))
      (node (ref "U2") (pin "78") (pinfunction "PC10/USART4_TX/SDIO_D2/(USART3_TX)_78") (pintype "passive"))
      (node (ref "U5") (pin "1") (pinfunction "DAT2_1") (pintype "passive"))
    )
    (net (code "67") (name "/PC11") (class "Default")
      (node (ref "J3") (pin "28") (pinfunction "28_28") (pintype "passive"))
      (node (ref "R24") (pin "1") (pinfunction "1_1") (pintype "passive"))
      (node (ref "U2") (pin "79") (pinfunction "PC11/USART4_RX/SDIO_D3/(USART3_RX)_79") (pintype "passive"))
      (node (ref "U5") (pin "2") (pinfunction "CD/DAT3_2") (pintype "passive"))
    )
    (net (code "68") (name "/PC12") (class "Default")
      (node (ref "J3") (pin "27") (pinfunction "27_27") (pintype "passive"))
      (node (ref "R27") (pin "1") (pinfunction "1_1") (pintype "passive"))
      (node (ref "U2") (pin "80") (pinfunction "PC12/UART5_TX/SDIO_CK/(USART3_CK)_80") (pintype "passive"))
      (node (ref "U5") (pin "5") (pinfunction "CLK_5") (pintype "passive"))
    )
    (net (code "69") (name "/PC13") (class "Default")
      (node (ref "J2") (pin "16") (pinfunction "16_16") (pintype "passive"))
      (node (ref "U2") (pin "7") (pinfunction "PC13/TAMPER-RTC_7") (pintype "passive"))
    )
    (net (code "70") (name "/PC14") (class "Default")
      (node (ref "C8") (pin "2") (pintype "passive"))
      (node (ref "U2") (pin "8") (pinfunction "PC14/OSC32_IN_8") (pintype "passive"))
      (node (ref "Y1") (pin "2") (pintype "passive"))
    )
    (net (code "71") (name "/PC15") (class "Default")
      (node (ref "C9") (pin "2") (pintype "passive"))
      (node (ref "U2") (pin "9") (pinfunction "PC15/OSC32_OUT_9") (pintype "passive"))
      (node (ref "Y1") (pin "1") (pintype "passive"))
    )
    (net (code "72") (name "/PD2") (class "Default")
      (node (ref "J3") (pin "24") (pinfunction "24_24") (pintype "passive"))
      (node (ref "R26") (pin "1") (pinfunction "1_1") (pintype "passive"))
      (node (ref "U2") (pin "83") (pinfunction "PD2/UART5_RX/TIM3_ETR/SDIO_CMD_83") (pintype "passive"))
      (node (ref "U5") (pin "3") (pinfunction "CMD_3") (pintype "passive"))
    )
    (net (code "73") (name "/PD3") (class "Default")
      (node (ref "J3") (pin "23") (pinfunction "23_23") (pintype "passive"))
      (node (ref "U2") (pin "84") (pinfunction "PD3/FSMC_CLK/(USART2_CTS)_84") (pintype "passive"))
    )
    (net (code "74") (name "/PD6") (class "Default")
      (node (ref "J3") (pin "20") (pinfunction "20_20") (pintype "passive"))
      (node (ref "U2") (pin "87") (pinfunction "PD6/FSMC_NWAIT/(USART2_RX)_87") (pintype "passive"))
    )
    (net (code "75") (name "/PD11") (class "Default")
      (node (ref "J3") (pin "44") (pinfunction "44_44") (pintype "passive"))
      (node (ref "U2") (pin "58") (pinfunction "PD11/FSMC_A16/(USART3_CTS)_58") (pintype "passive"))
    )
    (net (code "76") (name "/PD12") (class "Default")
      (node (ref "J3") (pin "43") (pinfunction "43_43") (pintype "passive"))
      (node (ref "U2") (pin "59") (pinfunction "PD12/FSMC_A17/(USART3_RTS/TIM4_CH1)_59") (pintype "passive"))
    )
    (net (code "77") (name "/PE0") (class "Default")
      (node (ref "J3") (pin "12") (pinfunction "12_12") (pintype "passive"))
      (node (ref "U2") (pin "97") (pinfunction "TIM4_ETR/FSMC_NBL0/PE0_97") (pintype "passive"))
    )
    (net (code "78") (name "/PE1") (class "Default")
      (node (ref "J3") (pin "11") (pinfunction "11_11") (pintype "passive"))
      (node (ref "U2") (pin "98") (pinfunction "FSMC_NBL1/PE1_98") (pintype "passive"))
    )
    (net (code "79") (name "/PE2") (class "Default")
      (node (ref "J2") (pin "11") (pinfunction "11_11") (pintype "passive"))
      (node (ref "U2") (pin "1") (pinfunction "TRACECLK/FSMC_A23/PE2_1") (pintype "passive"))
    )
    (net (code "80") (name "/PE5") (class "Default")
      (node (ref "J2") (pin "14") (pinfunction "14_14") (pintype "passive"))
      (node (ref "U2") (pin "4") (pinfunction "TRACED2/FSMC_A21/PE5_4") (pintype "passive"))
    )
    (net (code "81") (name "/PE6") (class "Default")
      (node (ref "J2") (pin "15") (pinfunction "15_15") (pintype "passive"))
      (node (ref "U2") (pin "5") (pinfunction "TRACED3/FSMC_A22/PE6_5") (pintype "passive"))
    )
    (net (code "82") (name "/RST") (class "Default")
      (node (ref "C6") (pin "2") (pinfunction "2_2") (pintype "passive"))
      (node (ref "J1") (pin "2") (pinfunction "2_2") (pintype "passive"))
      (node (ref "P1") (pin "15") (pinfunction "nSRST_15") (pintype "passive"))
      (node (ref "R6") (pin "2") (pinfunction "2_2") (pintype "passive"))
      (node (ref "RST") (pin "2") (pinfunction "2_2") (pintype "passive"))
      (node (ref "U2") (pin "14") (pinfunction "NRST_14") (pintype "passive"))
    )
    (net (code "83") (name "/VBAT") (class "Default")
      (node (ref "C7") (pin "2") (pinfunction "2_2") (pintype "passive"))
      (node (ref "Q1") (pin "3") (pinfunction "3_3") (pintype "passive"))
      (node (ref "U2") (pin "6") (pinfunction "VBAT_6") (pintype "passive"))
    )
    (net (code "84") (name "/VREF+") (class "Default")
      (node (ref "J2") (pin "22") (pinfunction "22_22") (pintype "passive"))
      (node (ref "R11") (pin "1") (pinfunction "1_1") (pintype "passive"))
      (node (ref "U2") (pin "21") (pinfunction "VREF+_21") (pintype "passive"))
    )
    (net (code "85") (name "/VREF-") (class "Default")
      (node (ref "C23") (pin "2") (pinfunction "2_2") (pintype "passive"))
      (node (ref "C24") (pin "2") (pinfunction "2_2") (pintype "passive"))
      (node (ref "J2") (pin "21") (pinfunction "21_21") (pintype "passive"))
      (node (ref "R35") (pin "1") (pinfunction "1_1") (pintype "passive"))
      (node (ref "U2") (pin "20") (pinfunction "VREF-_20") (pintype "passive"))
    )
    (net (code "86") (name "3V3") (class "Default")
      (node (ref "C1") (pin "2") (pinfunction "2_2") (pintype "passive"))
      (node (ref "C12") (pin "1") (pinfunction "1_1") (pintype "passive"))
      (node (ref "C13") (pin "1") (pinfunction "1_1") (pintype "passive"))
      (node (ref "C14") (pin "1") (pinfunction "1_1") (pintype "passive"))
      (node (ref "C15") (pin "1") (pinfunction "1_1") (pintype "passive"))
      (node (ref "C16") (pin "1") (pinfunction "1_1") (pintype "passive"))
      (node (ref "C17") (pin "1") (pinfunction "1_1") (pintype "passive"))
      (node (ref "C18") (pin "1") (pinfunction "1_1") (pintype "passive"))
      (node (ref "C19") (pin "1") (pinfunction "1_1") (pintype "passive"))
      (node (ref "C2") (pin "1") (pintype "passive"))
      (node (ref "C20") (pin "2") (pinfunction "2_2") (pintype "passive"))
      (node (ref "C4") (pin "1") (pinfunction "1_1") (pintype "passive"))
      (node (ref "D2") (pin "1") (pinfunction "1_1") (pintype "passive"))
      (node (ref "D3") (pin "1") (pinfunction "1_1") (pintype "passive"))
      (node (ref "J1") (pin "31") (pinfunction "31_31") (pintype "passive"))
      (node (ref "J2") (pin "5") (pinfunction "5_5") (pintype "passive"))
      (node (ref "J2") (pin "6") (pinfunction "6_6") (pintype "passive"))
      (node (ref "J2") (pin "7") (pinfunction "7_7") (pintype "passive"))
      (node (ref "J2") (pin "8") (pinfunction "8_8") (pintype "passive"))
      (node (ref "J3") (pin "1") (pinfunction "1_1") (pintype "passive"))
      (node (ref "J3") (pin "2") (pinfunction "2_2") (pintype "passive"))
      (node (ref "J3") (pin "3") (pinfunction "3_3") (pintype "passive"))
      (node (ref "J3") (pin "4") (pinfunction "4_4") (pintype "passive"))
      (node (ref "JP2") (pin "2") (pinfunction "2_2") (pintype "passive"))
      (node (ref "P1") (pin "1") (pinfunction "Vref_1") (pintype "passive"))
      (node (ref "P1") (pin "2") (pinfunction "Vsupply_2") (pintype "passive"))
      (node (ref "Q1") (pin "1") (pinfunction "1_1") (pintype "passive"))
      (node (ref "Q2") (pin "2") (pinfunction "E_2") (pintype "passive"))
      (node (ref "R1") (pin "1") (pinfunction "1_1") (pintype "passive"))
      (node (ref "R12") (pin "2") (pinfunction "2_2") (pintype "passive"))
      (node (ref "R16") (pin "2") (pinfunction "2_2") (pintype "passive"))
      (node (ref "R2") (pin "1") (pinfunction "1_1") (pintype "passive"))
      (node (ref "R20") (pin "1") (pinfunction "1_1") (pintype "passive"))
      (node (ref "R21") (pin "2") (pinfunction "2_2") (pintype "passive"))
      (node (ref "R24") (pin "2") (pinfunction "2_2") (pintype "passive"))
      (node (ref "R26") (pin "2") (pinfunction "2_2") (pintype "passive"))
      (node (ref "R27") (pin "2") (pinfunction "2_2") (pintype "passive"))
      (node (ref "R28") (pin "2") (pinfunction "2_2") (pintype "passive"))
      (node (ref "R29") (pin "2") (pinfunction "2_2") (pintype "passive"))
      (node (ref "R3") (pin "1") (pinfunction "1_1") (pintype "passive"))
      (node (ref "R34") (pin "2") (pinfunction "2_2") (pintype "passive"))
      (node (ref "R4") (pin "1") (pinfunction "1_1") (pintype "passive"))
      (node (ref "R5") (pin "2") (pinfunction "2_2") (pintype "passive"))
      (node (ref "R6") (pin "1") (pinfunction "1_1") (pintype "passive"))
      (node (ref "U1") (pin "2") (pinfunction "OUT_2") (pintype "passive"))
      (node (ref "U2") (pin "100") (pinfunction "VDD_3_100") (pintype "passive"))
      (node (ref "U2") (pin "11") (pinfunction "VDD_5_11") (pintype "passive"))
      (node (ref "U2") (pin "28") (pinfunction "VDD_4_28") (pintype "passive"))
      (node (ref "U2") (pin "50") (pinfunction "VDD_1_50") (pintype "passive"))
      (node (ref "U2") (pin "75") (pinfunction "VDD_2_75") (pintype "passive"))
      (node (ref "U3") (pin "3") (pinfunction "WP_3") (pintype "passive"))
      (node (ref "U3") (pin "7") (pinfunction "HOLD_7") (pintype "passive"))
      (node (ref "U3") (pin "8") (pinfunction "VCC_8") (pintype "passive"))
      (node (ref "U5") (pin "4") (pinfunction "VCC_4") (pintype "passive"))
    )
    (net (code "87") (name "5V") (class "Default")
      (node (ref "C3") (pin "1") (pinfunction "1_1") (pintype "passive"))
      (node (ref "C5") (pin "1") (pintype "passive"))
      (node (ref "J2") (pin "1") (pinfunction "1_1") (pintype "passive"))
      (node (ref "J2") (pin "2") (pinfunction "2_2") (pintype "passive"))
      (node (ref "J2") (pin "3") (pinfunction "3_3") (pintype "passive"))
      (node (ref "J2") (pin "4") (pinfunction "4_4") (pintype "passive"))
      (node (ref "J6") (pin "1") (pinfunction "1_1") (pintype "passive"))
      (node (ref "R25") (pin "1") (pinfunction "1_1") (pintype "passive"))
      (node (ref "U1") (pin "3") (pinfunction "VCC_3") (pintype "passive"))
    )
    (net (code "88") (name "GND") (class "Default")
      (node (ref "B1") (pin "2") (pintype "passive"))
      (node (ref "C1") (pin "1") (pinfunction "1_1") (pintype "passive"))
      (node (ref "C10") (pin "1") (pinfunction "1_1") (pintype "passive"))
      (node (ref "C11") (pin "2") (pinfunction "2_2") (pintype "passive"))
      (node (ref "C12") (pin "2") (pinfunction "2_2") (pintype "passive"))
      (node (ref "C13") (pin "2") (pinfunction "2_2") (pintype "passive"))
      (node (ref "C14") (pin "2") (pinfunction "2_2") (pintype "passive"))
      (node (ref "C15") (pin "2") (pinfunction "2_2") (pintype "passive"))
      (node (ref "C16") (pin "2") (pinfunction "2_2") (pintype "passive"))
      (node (ref "C17") (pin "2") (pinfunction "2_2") (pintype "passive"))
      (node (ref "C18") (pin "2") (pinfunction "2_2") (pintype "passive"))
      (node (ref "C19") (pin "2") (pinfunction "2_2") (pintype "passive"))
      (node (ref "C2") (pin "2") (pintype "passive"))
      (node (ref "C20") (pin "1") (pinfunction "1_1") (pintype "passive"))
      (node (ref "C21") (pin "1") (pinfunction "1_1") (pintype "passive"))
      (node (ref "C22") (pin "1") (pinfunction "1_1") (pintype "passive"))
      (node (ref "C3") (pin "2") (pinfunction "2_2") (pintype "passive"))
      (node (ref "C4") (pin "2") (pinfunction "2_2") (pintype "passive"))
      (node (ref "C5") (pin "2") (pintype "passive"))
      (node (ref "C6") (pin "1") (pinfunction "1_1") (pintype "passive"))
      (node (ref "C7") (pin "1") (pinfunction "1_1") (pintype "passive"))
      (node (ref "C8") (pin "1") (pintype "passive"))
      (node (ref "C9") (pin "1") (pintype "passive"))
      (node (ref "D1") (pin "2") (pinfunction "2_2") (pintype "passive"))
      (node (ref "J1") (pin "1") (pinfunction "1_1") (pintype "passive"))
      (node (ref "J1") (pin "30") (pinfunction "30_30") (pintype "passive"))
      (node (ref "J1") (pin "32") (pinfunction "32_32") (pintype "passive"))
      (node (ref "J2") (pin "10") (pinfunction "10_10") (pintype "passive"))
      (node (ref "J2") (pin "9") (pinfunction "9_9") (pintype "passive"))
      (node (ref "J3") (pin "10") (pinfunction "10_10") (pintype "passive"))
      (node (ref "J3") (pin "7") (pinfunction "7_7") (pintype "passive"))
      (node (ref "J3") (pin "8") (pinfunction "8_8") (pintype "passive"))
      (node (ref "J3") (pin "9") (pinfunction "9_9") (pintype "passive"))
      (node (ref "J4") (pin "5") (pinfunction "GND_5") (pintype "passive"))
      (node (ref "J6") (pin "2") (pinfunction "2_2") (pintype "passive"))
      (node (ref "JP2") (pin "1") (pinfunction "1_1") (pintype "passive"))
      (node (ref "K0") (pin "2") (pinfunction "2_2") (pintype "passive"))
      (node (ref "K1") (pin "2") (pinfunction "2_2") (pintype "passive"))
      (node (ref "P1") (pin "10") (pinfunction "GND_10") (pintype "passive"))
      (node (ref "P1") (pin "12") (pinfunction "GND_12") (pintype "passive"))
      (node (ref "P1") (pin "14") (pinfunction "GND_14") (pintype "passive"))
      (node (ref "P1") (pin "16") (pinfunction "GND_16") (pintype "passive"))
      (node (ref "P1") (pin "18") (pinfunction "GND_18") (pintype "passive"))
      (node (ref "P1") (pin "20") (pinfunction "GND_20") (pintype "passive"))
      (node (ref "P1") (pin "4") (pinfunction "GND_4") (pintype "passive"))
      (node (ref "P1") (pin "6") (pinfunction "GND_6") (pintype "passive"))
      (node (ref "P1") (pin "8") (pinfunction "GND_8") (pintype "passive"))
      (node (ref "R32") (pin "2") (pinfunction "2_2") (pintype "passive"))
      (node (ref "R35") (pin "2") (pinfunction "2_2") (pintype "passive"))
      (node (ref "R7") (pin "1") (pinfunction "1_1") (pintype "passive"))
      (node (ref "R8") (pin "1") (pinfunction "1_1") (pintype "passive"))
      (node (ref "R9") (pin "1") (pinfunction "1_1") (pintype "passive"))
      (node (ref "RST") (pin "1") (pinfunction "1_1") (pintype "passive"))
      (node (ref "U1") (pin "1") (pinfunction "GND_1") (pintype "passive"))
      (node (ref "U2") (pin "10") (pinfunction "VSS_5_10") (pintype "passive"))
      (node (ref "U2") (pin "27") (pinfunction "VSS_4_27") (pintype "passive"))
      (node (ref "U2") (pin "74") (pinfunction "VSS_2_74") (pintype "passive"))
      (node (ref "U2") (pin "99") (pinfunction "VSS_3_99") (pintype "passive"))
      (node (ref "U3") (pin "4") (pinfunction "GND_4") (pintype "passive"))
      (node (ref "U5") (pin "6") (pinfunction "GND_6") (pintype "passive"))
      (node (ref "U5") (pin "9") (pinfunction "NC_9") (pintype "passive"))
    )
    (net (code "89") (name "Net-(B1-Pad1)") (class "Default")
      (node (ref "B1") (pin "1") (pintype "passive"))
      (node (ref "Q1") (pin "2") (pinfunction "2_2") (pintype "passive"))
    )
    (net (code "90") (name "Net-(D1-Pad1)") (class "Default")
      (node (ref "D1") (pin "1") (pinfunction "1_1") (pintype "passive"))
      (node (ref "R5") (pin "1") (pinfunction "1_1") (pintype "passive"))
    )
    (net (code "91") (name "Net-(D2-Pad2)") (class "Default")
      (node (ref "D2") (pin "2") (pinfunction "2_2") (pintype "passive"))
      (node (ref "R13") (pin "2") (pinfunction "2_2") (pintype "passive"))
    )
    (net (code "92") (name "Net-(D3-Pad2)") (class "Default")
      (node (ref "D3") (pin "2") (pinfunction "2_2") (pintype "passive"))
      (node (ref "R14") (pin "2") (pinfunction "2_2") (pintype "passive"))
    )
    (net (code "93") (name "Net-(J1-Pad27)") (class "Default")
      (node (ref "J1") (pin "27") (pinfunction "27_27") (pintype "passive"))
      (node (ref "R17") (pin "1") (pinfunction "1_1") (pintype "passive"))
    )
    (net (code "94") (name "Net-(J3-Pad5)") (class "Default")
      (node (ref "J3") (pin "5") (pinfunction "5_5") (pintype "passive"))
      (node (ref "R23") (pin "2") (pinfunction "2_2") (pintype "passive"))
    )
    (net (code "95") (name "Net-(J3-Pad6)") (class "Default")
      (node (ref "J3") (pin "6") (pinfunction "6_6") (pintype "passive"))
      (node (ref "R33") (pin "1") (pinfunction "1_1") (pintype "passive"))
    )
    (net (code "96") (name "Net-(J4-D+)") (class "Default")
      (node (ref "J4") (pin "3") (pinfunction "D+_3") (pintype "passive"))
      (node (ref "R19") (pin "1") (pinfunction "1_1") (pintype "passive"))
      (node (ref "R21") (pin "1") (pinfunction "1_1") (pintype "passive"))
    )
    (net (code "97") (name "Net-(J4-D-)") (class "Default")
      (node (ref "J4") (pin "2") (pinfunction "D-_2") (pintype "passive"))
      (node (ref "R18") (pin "1") (pinfunction "1_1") (pintype "passive"))
    )
    (net (code "98") (name "Net-(J4-VDD)") (class "Default")
      (node (ref "J4") (pin "1") (pinfunction "VDD_1") (pintype "passive"))
      (node (ref "R25") (pin "2") (pinfunction "2_2") (pintype "passive"))
    )
    (net (code "99") (name "Net-(K_UP-Pad1)") (class "Default")
      (node (ref "K_UP") (pin "1") (pinfunction "1_1") (pintype "passive"))
      (node (ref "R16") (pin "1") (pinfunction "1_1") (pintype "passive"))
    )
    (net (code "100") (name "Net-(Q2-B)") (class "Default")
      (node (ref "Q2") (pin "1") (pinfunction "B_1") (pintype "passive"))
      (node (ref "R30") (pin "1") (pinfunction "1_1") (pintype "passive"))
      (node (ref "R31") (pin "2") (pinfunction "2_2") (pintype "passive"))
    )
    (net (code "101") (name "Net-(Q2-C)") (class "Default")
      (node (ref "J1") (pin "28") (pinfunction "28_28") (pintype "passive"))
      (node (ref "Q2") (pin "3") (pinfunction "C_3") (pintype "passive"))
      (node (ref "R31") (pin "1") (pinfunction "1_1") (pintype "passive"))
      (node (ref "R32") (pin "1") (pinfunction "1_1") (pintype "passive"))
    )
    (net (code "102") (name "Net-(U2-OSC_IN)") (class "Default")
      (node (ref "C10") (pin "2") (pinfunction "2_2") (pintype "passive"))
      (node (ref "R10") (pin "1") (pinfunction "1_1") (pintype "passive"))
      (node (ref "U2") (pin "12") (pinfunction "OSC_IN_12") (pintype "passive"))
      (node (ref "Y2") (pin "1") (pinfunction "1_1") (pintype "passive"))
    )
    (net (code "103") (name "Net-(U2-OSC_OUT)") (class "Default")
      (node (ref "C11") (pin "1") (pinfunction "1_1") (pintype "passive"))
      (node (ref "R10") (pin "2") (pinfunction "2_2") (pintype "passive"))
      (node (ref "U2") (pin "13") (pinfunction "OSC_OUT_13") (pintype "passive"))
      (node (ref "Y2") (pin "2") (pinfunction "2_2") (pintype "passive"))
    )
    (net (code "104") (name "Net-(U2-VCAP_1)") (class "Default")
      (node (ref "C21") (pin "2") (pinfunction "2_2") (pintype "passive"))
      (node (ref "U2") (pin "49") (pinfunction "VCAP_1_49") (pintype "passive"))
    )
    (net (code "105") (name "Net-(U2-VCAP_2)") (class "Default")
      (node (ref "C22") (pin "2") (pinfunction "2_2") (pintype "passive"))
      (node (ref "U2") (pin "73") (pinfunction "VCAP_2_73") (pintype "passive"))
    )
    (net (code "106") (name "Net-(U3-CLK)") (class "Default")
      (node (ref "R22") (pin "1") (pinfunction "1_1") (pintype "passive"))
      (node (ref "U3") (pin "6") (pinfunction "CLK_6") (pintype "passive"))
    )
    (net (code "107") (name "VDDA") (class "Default")
      (node (ref "C23") (pin "1") (pinfunction "1_1") (pintype "passive"))
      (node (ref "C24") (pin "1") (pinfunction "1_1") (pintype "passive"))
      (node (ref "R11") (pin "2") (pinfunction "2_2") (pintype "passive"))
      (node (ref "R34") (pin "1") (pinfunction "1_1") (pintype "passive"))
      (node (ref "U2") (pin "19") (pinfunction "VDD_19") (pintype "passive"))
      (node (ref "U2") (pin "22") (pinfunction "VDDA_22") (pintype "passive"))
    )
    (net (code "108") (name "unconnected-(J1-Pad29)") (class "Default")
      (node (ref "J1") (pin "29") (pinfunction "29_29") (pintype "passive"))
    )
    (net (code "109") (name "unconnected-(J4-NCC-Pad4)") (class "Default")
      (node (ref "J4") (pin "4") (pinfunction "NCC_4") (pintype "passive"))
    )
    (net (code "110") (name "unconnected-(P1-NC-Pad17)") (class "Default")
      (node (ref "P1") (pin "17") (pinfunction "NC_17") (pintype "passive"))
    )
    (net (code "111") (name "unconnected-(P1-NC-Pad19)") (class "Default")
      (node (ref "P1") (pin "19") (pinfunction "NC_19") (pintype "passive"))
    )
    (net (code "112") (name "unconnected-(P1-RTCK-Pad11)") (class "Default")
      (node (ref "P1") (pin "11") (pinfunction "RTCK_11") (pintype "passive"))
    )
  )
)
